# GBxProg.net
KiCad netlist of a schematic drawn in Altium Designer
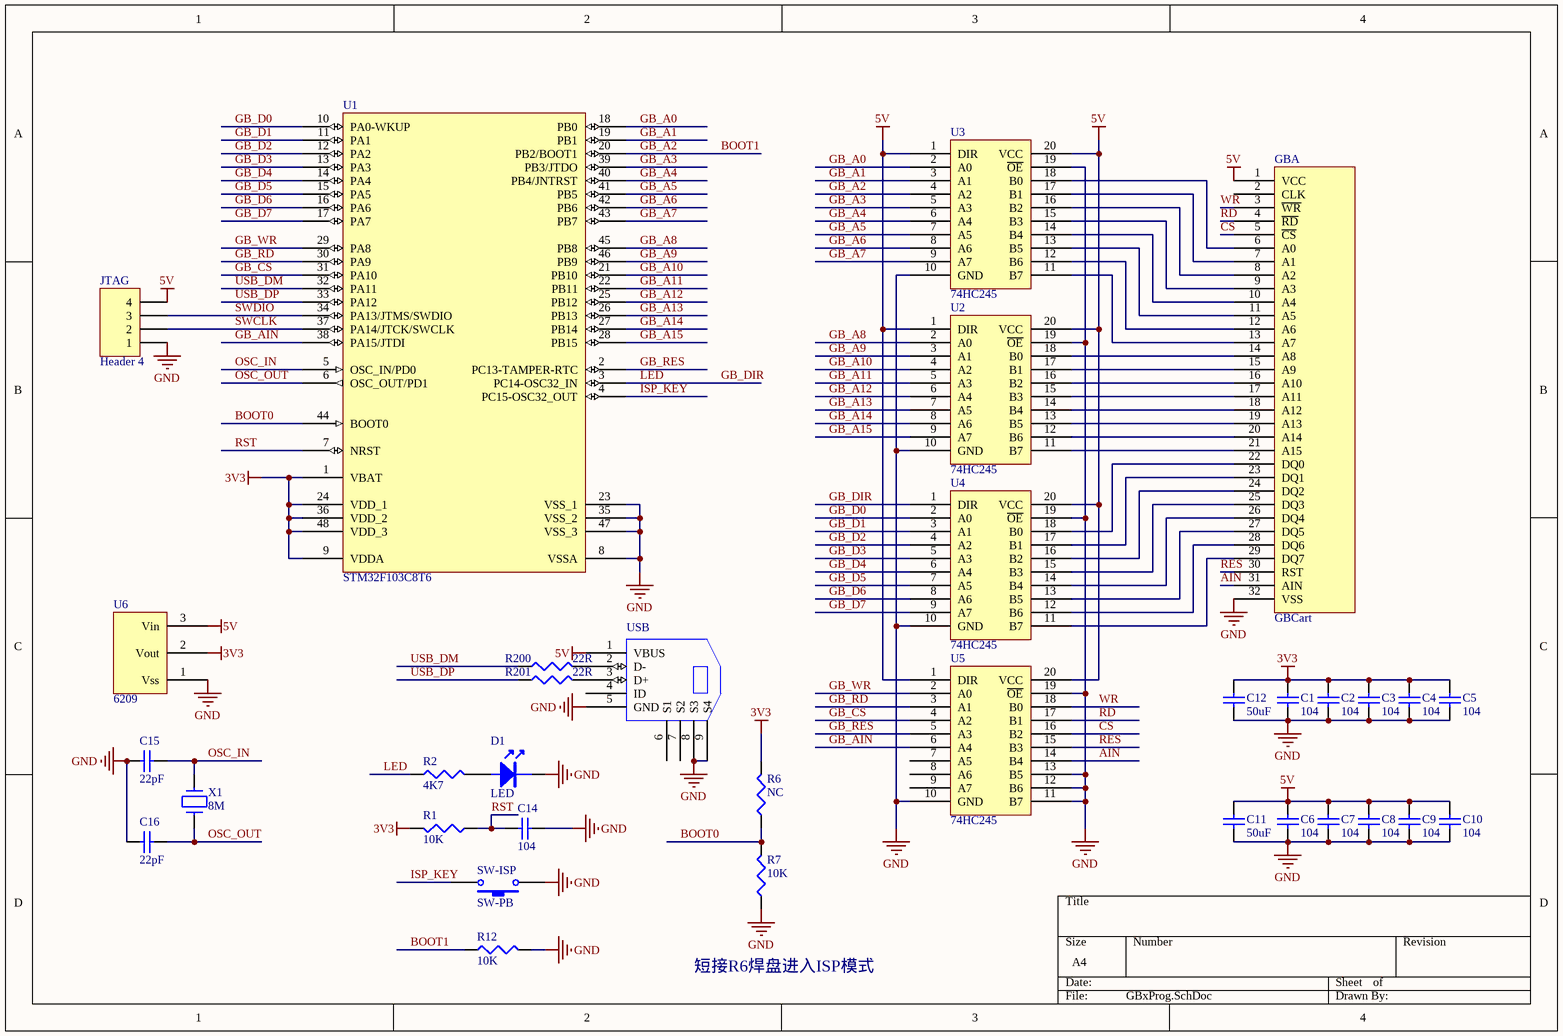
[diagram p0: GBxProg.SchDoc]

(export (version "E")
  (design (tool "Eeschema 10.0.6"))
  (components
    (comp (ref "C1")
      (value "104")
      (footprint "1608[0603]")
      (description "Capacitor (Semiconductor SIM Model)")
      (fields (field (name "PUBLISHER") "Altium Limited"))
      (libsource (lib "Miscellaneous Devices") (part "Cap Semi"))
    )
    (comp (ref "C2")
      (value "104")
      (footprint "1608[0603]")
      (description "Capacitor (Semiconductor SIM Model)")
      (fields (field (name "PUBLISHER") "Altium Limited"))
      (libsource (lib "Miscellaneous Devices") (part "Cap Semi"))
    )
    (comp (ref "C3")
      (value "104")
      (footprint "1608[0603]")
      (description "Capacitor (Semiconductor SIM Model)")
      (fields (field (name "PUBLISHER") "Altium Limited"))
      (libsource (lib "Miscellaneous Devices") (part "Cap Semi"))
    )
    (comp (ref "C4")
      (value "104")
      (footprint "1608[0603]")
      (description "Capacitor (Semiconductor SIM Model)")
      (fields (field (name "PUBLISHER") "Altium Limited"))
      (libsource (lib "Miscellaneous Devices") (part "Cap Semi"))
    )
    (comp (ref "C5")
      (value "104")
      (footprint "1608[0603]")
      (description "Capacitor (Semiconductor SIM Model)")
      (fields (field (name "PUBLISHER") "Altium Limited"))
      (libsource (lib "Miscellaneous Devices") (part "Cap Semi"))
    )
    (comp (ref "C6")
      (value "104")
      (footprint "1608[0603]")
      (description "Capacitor (Semiconductor SIM Model)")
      (fields (field (name "PUBLISHER") "Altium Limited"))
      (libsource (lib "Miscellaneous Devices") (part "Cap Semi"))
    )
    (comp (ref "C7")
      (value "104")
      (footprint "1608[0603]")
      (description "Capacitor (Semiconductor SIM Model)")
      (fields (field (name "PUBLISHER") "Altium Limited"))
      (libsource (lib "Miscellaneous Devices") (part "Cap Semi"))
    )
    (comp (ref "C8")
      (value "104")
      (footprint "1608[0603]")
      (description "Capacitor (Semiconductor SIM Model)")
      (fields (field (name "PUBLISHER") "Altium Limited"))
      (libsource (lib "Miscellaneous Devices") (part "Cap Semi"))
    )
    (comp (ref "C9")
      (value "104")
      (footprint "1608[0603]")
      (description "Capacitor (Semiconductor SIM Model)")
      (fields (field (name "PUBLISHER") "Altium Limited"))
      (libsource (lib "Miscellaneous Devices") (part "Cap Semi"))
    )
    (comp (ref "C10")
      (value "104")
      (footprint "1608[0603]")
      (description "Capacitor (Semiconductor SIM Model)")
      (fields (field (name "PUBLISHER") "Altium Limited"))
      (libsource (lib "Miscellaneous Devices") (part "Cap Semi"))
    )
    (comp (ref "C11")
      (value "50uF")
      (footprint "C1206")
      (description "Capacitor (Semiconductor SIM Model)")
      (fields (field (name "PUBLISHER") "Altium Limited"))
      (libsource (lib "Miscellaneous Devices") (part "Cap Semi"))
    )
    (comp (ref "C12")
      (value "50uF")
      (footprint "C1206")
      (description "Capacitor (Semiconductor SIM Model)")
      (fields (field (name "PUBLISHER") "Altium Limited"))
      (libsource (lib "Miscellaneous Devices") (part "Cap Semi"))
    )
    (comp (ref "C14")
      (value "104")
      (footprint "1608[0603]")
      (description "Capacitor (Semiconductor SIM Model)")
      (fields (field (name "PUBLISHER") "Altium Limited"))
      (libsource (lib "Miscellaneous Devices") (part "Cap Semi"))
    )
    (comp (ref "C15")
      (value "22pF")
      (footprint "1608[0603]")
      (description "Capacitor (Semiconductor SIM Model)")
      (fields (field (name "PUBLISHER") "Altium Limited"))
      (libsource (lib "Miscellaneous Devices") (part "Cap Semi"))
    )
    (comp (ref "C16")
      (value "22pF")
      (footprint "1608[0603]")
      (description "Capacitor (Semiconductor SIM Model)")
      (fields (field (name "PUBLISHER") "Altium Limited"))
      (libsource (lib "Miscellaneous Devices") (part "Cap Semi"))
    )
    (comp (ref "D1") (value "LED") (footprint "0805D") (libsource (lib "Schlib1") (part "LED")))
    (comp (ref "GBA") (value "GBCart") (footprint "GB_CART_1") (libsource (lib "Schlib1") (part "GBCart")))
    (comp (ref "JTAG")
      (value "Header 4")
      (footprint "HDR1X4")
      (description "Header, 4-Pin")
      (fields (field (name "PUBLISHER") "Altium Limited"))
      (libsource (lib "Miscellaneous Connectors") (part "Header 4"))
    )
    (comp (ref "R1")
      (value "10K")
      (footprint "J1-0603")
      (description "Resistor")
      (fields (field (name "PUBLISHER") "Altium Limited"))
      (libsource (lib "Miscellaneous Devices") (part "Res3"))
    )
    (comp (ref "R2")
      (value "4K7")
      (footprint "J1-0603")
      (description "Resistor")
      (fields (field (name "PUBLISHER") "Altium Limited"))
      (libsource (lib "Miscellaneous Devices") (part "Res3"))
    )
    (comp (ref "R6")
      (value "NC")
      (footprint "J1-0603")
      (description "Resistor")
      (fields (field (name "PUBLISHER") "Altium Limited"))
      (libsource (lib "Miscellaneous Devices") (part "Res3"))
    )
    (comp (ref "R7")
      (value "10K")
      (footprint "J1-0603")
      (description "Resistor")
      (fields (field (name "PUBLISHER") "Altium Limited"))
      (libsource (lib "Miscellaneous Devices") (part "Res3"))
    )
    (comp (ref "R12")
      (value "10K")
      (footprint "J1-0603")
      (description "Resistor")
      (fields (field (name "PUBLISHER") "Altium Limited"))
      (libsource (lib "Miscellaneous Devices") (part "Res3"))
    )
    (comp (ref "R200")
      (value "22R")
      (footprint "J1-0603")
      (description "Resistor")
      (fields (field (name "PUBLISHER") "Altium Limited"))
      (libsource (lib "Miscellaneous Devices") (part "Res3"))
    )
    (comp (ref "R201")
      (value "22R")
      (footprint "J1-0603")
      (description "Resistor")
      (fields (field (name "PUBLISHER") "Altium Limited"))
      (libsource (lib "Miscellaneous Devices") (part "Res3"))
    )
    (comp (ref "SW-ISP")
      (value "SW-PB")
      (footprint "SOP2")
      (description "Switch")
      (fields (field (name "PUBLISHER") "Altium Limited"))
      (libsource (lib "Miscellaneous Devices") (part "SW-PB"))
    )
    (comp (ref "U1")
      (value "STM32F103C8T6")
      (footprint "LQFP48_N")
      (description "STM32 ARM-based 32-bit MCU with 64 Kbytes Flash, 48-pin LQFP, Industrial Temperature")
      (fields (field (name "PUBLISHER") "*"))
      (libsource (lib "Schlib1") (part "STM32F103C8T6"))
    )
    (comp (ref "U2") (value "74HC245") (footprint "TSSOP20") (libsource (lib "Schlib1") (part "74HC245")))
    (comp (ref "U3") (value "74HC245") (footprint "TSSOP20") (libsource (lib "Schlib1") (part "74HC245")))
    (comp (ref "U4") (value "74HC245") (footprint "TSSOP20") (libsource (lib "Schlib1") (part "74HC245")))
    (comp (ref "U5") (value "74HC245") (footprint "TSSOP20") (libsource (lib "Schlib1") (part "74HC245")))
    (comp (ref "U6") (value "6209") (footprint "SOT-23") (libsource (lib "Schlib1") (part "6209")))
    (comp (ref "USB") (value "USB-MINIAB") (footprint "USB-MICRO") (libsource (lib "*") (part "USB-MINIAB")))
    (comp (ref "X1") (value "8M") (footprint "49S") (libsource (lib "常用元件库") (part "CRYSTAL")))
  )
  (nets
    (net (code "1") (name "/AIN") (class "Default")
      (node (ref "GBA") (pin "31") (pinfunction "AIN_31") (pintype "passive"))
      (node (ref "U5") (pin "14") (pinfunction "B4_14") (pintype "passive"))
    )
    (net (code "2") (name "/BOOT0") (class "Default")
      (node (ref "R6") (pin "1") (pinfunction "1_1") (pintype "passive"))
      (node (ref "R7") (pin "2") (pinfunction "2_2") (pintype "passive"))
      (node (ref "U1") (pin "44") (pinfunction "BOOT0_44") (pintype "input"))
    )
    (net (code "3") (name "/BOOT1") (class "Default")
      (node (ref "R12") (pin "1") (pinfunction "1_1") (pintype "passive"))
      (node (ref "U1") (pin "20") (pinfunction "PB2/BOOT1_20") (pintype "bidirectional"))
      (node (ref "U3") (pin "4") (pinfunction "A2_4") (pintype "passive"))
    )
    (net (code "4") (name "/CS") (class "Default")
      (node (ref "GBA") (pin "5") (pinfunction "~{CS}_5") (pintype "passive"))
      (node (ref "U5") (pin "16") (pinfunction "B2_16") (pintype "passive"))
    )
    (net (code "5") (name "/GB_A0") (class "Default")
      (node (ref "U1") (pin "18") (pinfunction "PB0_18") (pintype "bidirectional"))
      (node (ref "U3") (pin "2") (pinfunction "A0_2") (pintype "passive"))
    )
    (net (code "6") (name "/GB_A1") (class "Default")
      (node (ref "U1") (pin "19") (pinfunction "PB1_19") (pintype "bidirectional"))
      (node (ref "U3") (pin "3") (pinfunction "A1_3") (pintype "passive"))
    )
    (net (code "7") (name "/GB_A3") (class "Default")
      (node (ref "U1") (pin "39") (pinfunction "PB3/JTDO_39") (pintype "bidirectional"))
      (node (ref "U3") (pin "5") (pinfunction "A3_5") (pintype "passive"))
    )
    (net (code "8") (name "/GB_A4") (class "Default")
      (node (ref "U1") (pin "40") (pinfunction "PB4/JNTRST_40") (pintype "bidirectional"))
      (node (ref "U3") (pin "6") (pinfunction "A4_6") (pintype "passive"))
    )
    (net (code "9") (name "/GB_A5") (class "Default")
      (node (ref "U1") (pin "41") (pinfunction "PB5_41") (pintype "bidirectional"))
      (node (ref "U3") (pin "7") (pinfunction "A5_7") (pintype "passive"))
    )
    (net (code "10") (name "/GB_A6") (class "Default")
      (node (ref "U1") (pin "42") (pinfunction "PB6_42") (pintype "bidirectional"))
      (node (ref "U3") (pin "8") (pinfunction "A6_8") (pintype "passive"))
    )
    (net (code "11") (name "/GB_A7") (class "Default")
      (node (ref "U1") (pin "43") (pinfunction "PB7_43") (pintype "bidirectional"))
      (node (ref "U3") (pin "9") (pinfunction "A7_9") (pintype "passive"))
    )
    (net (code "12") (name "/GB_A8") (class "Default")
      (node (ref "U1") (pin "45") (pinfunction "PB8_45") (pintype "bidirectional"))
      (node (ref "U2") (pin "2") (pinfunction "A0_2") (pintype "passive"))
    )
    (net (code "13") (name "/GB_A9") (class "Default")
      (node (ref "U1") (pin "46") (pinfunction "PB9_46") (pintype "bidirectional"))
      (node (ref "U2") (pin "3") (pinfunction "A1_3") (pintype "passive"))
    )
    (net (code "14") (name "/GB_A10") (class "Default")
      (node (ref "U1") (pin "21") (pinfunction "PB10_21") (pintype "bidirectional"))
      (node (ref "U2") (pin "4") (pinfunction "A2_4") (pintype "passive"))
    )
    (net (code "15") (name "/GB_A11") (class "Default")
      (node (ref "U1") (pin "22") (pinfunction "PB11_22") (pintype "bidirectional"))
      (node (ref "U2") (pin "5") (pinfunction "A3_5") (pintype "passive"))
    )
    (net (code "16") (name "/GB_A12") (class "Default")
      (node (ref "U1") (pin "25") (pinfunction "PB12_25") (pintype "bidirectional"))
      (node (ref "U2") (pin "6") (pinfunction "A4_6") (pintype "passive"))
    )
    (net (code "17") (name "/GB_A13") (class "Default")
      (node (ref "U1") (pin "26") (pinfunction "PB13_26") (pintype "bidirectional"))
      (node (ref "U2") (pin "7") (pinfunction "A5_7") (pintype "passive"))
    )
    (net (code "18") (name "/GB_A14") (class "Default")
      (node (ref "U1") (pin "27") (pinfunction "PB14_27") (pintype "bidirectional"))
      (node (ref "U2") (pin "8") (pinfunction "A6_8") (pintype "passive"))
    )
    (net (code "19") (name "/GB_A15") (class "Default")
      (node (ref "U1") (pin "28") (pinfunction "PB15_28") (pintype "bidirectional"))
      (node (ref "U2") (pin "9") (pinfunction "A7_9") (pintype "passive"))
    )
    (net (code "20") (name "/GB_AIN") (class "Default")
      (node (ref "U1") (pin "38") (pinfunction "PA15/JTDI_38") (pintype "bidirectional"))
      (node (ref "U5") (pin "6") (pinfunction "A4_6") (pintype "passive"))
    )
    (net (code "21") (name "/GB_CS") (class "Default")
      (node (ref "U1") (pin "31") (pinfunction "PA10_31") (pintype "bidirectional"))
      (node (ref "U5") (pin "4") (pinfunction "A2_4") (pintype "passive"))
    )
    (net (code "22") (name "/GB_D0") (class "Default")
      (node (ref "U1") (pin "10") (pinfunction "PA0-WKUP_10") (pintype "bidirectional"))
      (node (ref "U4") (pin "2") (pinfunction "A0_2") (pintype "passive"))
    )
    (net (code "23") (name "/GB_D1") (class "Default")
      (node (ref "U1") (pin "11") (pinfunction "PA1_11") (pintype "bidirectional"))
      (node (ref "U4") (pin "3") (pinfunction "A1_3") (pintype "passive"))
    )
    (net (code "24") (name "/GB_D2") (class "Default")
      (node (ref "U1") (pin "12") (pinfunction "PA2_12") (pintype "bidirectional"))
      (node (ref "U4") (pin "4") (pinfunction "A2_4") (pintype "passive"))
    )
    (net (code "25") (name "/GB_D3") (class "Default")
      (node (ref "U1") (pin "13") (pinfunction "PA3_13") (pintype "bidirectional"))
      (node (ref "U4") (pin "5") (pinfunction "A3_5") (pintype "passive"))
    )
    (net (code "26") (name "/GB_D4") (class "Default")
      (node (ref "U1") (pin "14") (pinfunction "PA4_14") (pintype "bidirectional"))
      (node (ref "U4") (pin "6") (pinfunction "A4_6") (pintype "passive"))
    )
    (net (code "27") (name "/GB_D5") (class "Default")
      (node (ref "U1") (pin "15") (pinfunction "PA5_15") (pintype "bidirectional"))
      (node (ref "U4") (pin "7") (pinfunction "A5_7") (pintype "passive"))
    )
    (net (code "28") (name "/GB_D6") (class "Default")
      (node (ref "U1") (pin "16") (pinfunction "PA6_16") (pintype "bidirectional"))
      (node (ref "U4") (pin "8") (pinfunction "A6_8") (pintype "passive"))
    )
    (net (code "29") (name "/GB_D7") (class "Default")
      (node (ref "U1") (pin "17") (pinfunction "PA7_17") (pintype "bidirectional"))
      (node (ref "U4") (pin "9") (pinfunction "A7_9") (pintype "passive"))
    )
    (net (code "30") (name "/GB_DIR") (class "Default")
      (node (ref "R2") (pin "1") (pinfunction "1_1") (pintype "passive"))
      (node (ref "U1") (pin "3") (pinfunction "PC14-OSC32_IN_3") (pintype "bidirectional"))
      (node (ref "U4") (pin "1") (pinfunction "DIR_1") (pintype "passive"))
    )
    (net (code "31") (name "/GB_RD") (class "Default")
      (node (ref "U1") (pin "30") (pinfunction "PA9_30") (pintype "bidirectional"))
      (node (ref "U5") (pin "3") (pinfunction "A1_3") (pintype "passive"))
    )
    (net (code "32") (name "/GB_RES") (class "Default")
      (node (ref "U1") (pin "2") (pinfunction "PC13-TAMPER-RTC_2") (pintype "bidirectional"))
      (node (ref "U5") (pin "5") (pinfunction "A3_5") (pintype "passive"))
    )
    (net (code "33") (name "/GB_WR") (class "Default")
      (node (ref "U1") (pin "29") (pinfunction "PA8_29") (pintype "bidirectional"))
      (node (ref "U5") (pin "2") (pinfunction "A0_2") (pintype "passive"))
    )
    (net (code "34") (name "/ISP_KEY") (class "Default")
      (node (ref "SW-ISP") (pin "2") (pinfunction "2_2") (pintype "passive"))
      (node (ref "U1") (pin "4") (pinfunction "PC15-OSC32_OUT_4") (pintype "bidirectional"))
    )
    (net (code "35") (name "/OSC_IN") (class "Default")
      (node (ref "C15") (pin "1") (pinfunction "1_1") (pintype "passive"))
      (node (ref "U1") (pin "5") (pinfunction "OSC_IN/PD0_5") (pintype "input"))
      (node (ref "X1") (pin "2") (pinfunction "2_2") (pintype "passive"))
    )
    (net (code "36") (name "/OSC_OUT") (class "Default")
      (node (ref "C16") (pin "1") (pinfunction "1_1") (pintype "passive"))
      (node (ref "U1") (pin "6") (pinfunction "OSC_OUT/PD1_6") (pintype "output"))
      (node (ref "X1") (pin "1") (pinfunction "1_1") (pintype "passive"))
    )
    (net (code "37") (name "/RD") (class "Default")
      (node (ref "GBA") (pin "4") (pinfunction "~{RD}_4") (pintype "passive"))
      (node (ref "U5") (pin "17") (pinfunction "B1_17") (pintype "passive"))
    )
    (net (code "38") (name "/RES") (class "Default")
      (node (ref "GBA") (pin "30") (pinfunction "RST_30") (pintype "passive"))
      (node (ref "U5") (pin "15") (pinfunction "B3_15") (pintype "passive"))
    )
    (net (code "39") (name "/RST") (class "Default")
      (node (ref "C14") (pin "2") (pinfunction "2_2") (pintype "passive"))
      (node (ref "R1") (pin "1") (pinfunction "1_1") (pintype "passive"))
      (node (ref "U1") (pin "7") (pinfunction "NRST_7") (pintype "bidirectional"))
    )
    (net (code "40") (name "/SWCLK") (class "Default")
      (node (ref "JTAG") (pin "2") (pinfunction "2_2") (pintype "passive"))
      (node (ref "U1") (pin "37") (pinfunction "PA14/JTCK/SWCLK_37") (pintype "bidirectional"))
    )
    (net (code "41") (name "/SWDIO") (class "Default")
      (node (ref "JTAG") (pin "3") (pinfunction "3_3") (pintype "passive"))
      (node (ref "U1") (pin "34") (pinfunction "PA13/JTMS/SWDIO_34") (pintype "bidirectional"))
    )
    (net (code "42") (name "/USB_DM") (class "Default")
      (node (ref "R200") (pin "1") (pinfunction "1_1") (pintype "passive"))
      (node (ref "U1") (pin "32") (pinfunction "PA11_32") (pintype "bidirectional"))
    )
    (net (code "43") (name "/USB_DP") (class "Default")
      (node (ref "R201") (pin "1") (pinfunction "1_1") (pintype "passive"))
      (node (ref "U1") (pin "33") (pinfunction "PA12_33") (pintype "bidirectional"))
    )
    (net (code "44") (name "/WR") (class "Default")
      (node (ref "GBA") (pin "3") (pinfunction "~{WR}_3") (pintype "passive"))
      (node (ref "U5") (pin "18") (pinfunction "B0_18") (pintype "passive"))
    )
    (net (code "45") (name "3V3") (class "Default")
      (node (ref "C1") (pin "2") (pinfunction "2_2") (pintype "passive"))
      (node (ref "C12") (pin "2") (pinfunction "2_2") (pintype "passive"))
      (node (ref "C2") (pin "2") (pinfunction "2_2") (pintype "passive"))
      (node (ref "C3") (pin "2") (pinfunction "2_2") (pintype "passive"))
      (node (ref "C4") (pin "2") (pinfunction "2_2") (pintype "passive"))
      (node (ref "C5") (pin "2") (pinfunction "2_2") (pintype "passive"))
      (node (ref "R1") (pin "2") (pinfunction "2_2") (pintype "passive"))
      (node (ref "R6") (pin "2") (pinfunction "2_2") (pintype "passive"))
      (node (ref "U1") (pin "1") (pinfunction "VBAT_1") (pintype "power_in"))
      (node (ref "U1") (pin "24") (pinfunction "VDD_1_24") (pintype "power_in"))
      (node (ref "U1") (pin "36") (pinfunction "VDD_2_36") (pintype "power_in"))
      (node (ref "U1") (pin "48") (pinfunction "VDD_3_48") (pintype "power_in"))
      (node (ref "U1") (pin "9") (pinfunction "VDDA_9") (pintype "power_in"))
      (node (ref "U6") (pin "2") (pinfunction "Vout_2") (pintype "passive"))
    )
    (net (code "46") (name "5V") (class "Default")
      (node (ref "C10") (pin "2") (pinfunction "2_2") (pintype "passive"))
      (node (ref "C11") (pin "2") (pinfunction "2_2") (pintype "passive"))
      (node (ref "C6") (pin "2") (pinfunction "2_2") (pintype "passive"))
      (node (ref "C7") (pin "2") (pinfunction "2_2") (pintype "passive"))
      (node (ref "C8") (pin "2") (pinfunction "2_2") (pintype "passive"))
      (node (ref "C9") (pin "2") (pinfunction "2_2") (pintype "passive"))
      (node (ref "GBA") (pin "1") (pinfunction "VCC_1") (pintype "passive"))
      (node (ref "JTAG") (pin "4") (pinfunction "4_4") (pintype "passive"))
      (node (ref "U2") (pin "1") (pinfunction "DIR_1") (pintype "passive"))
      (node (ref "U2") (pin "20") (pinfunction "VCC_20") (pintype "passive"))
      (node (ref "U3") (pin "1") (pinfunction "DIR_1") (pintype "passive"))
      (node (ref "U3") (pin "20") (pinfunction "VCC_20") (pintype "passive"))
      (node (ref "U4") (pin "20") (pinfunction "VCC_20") (pintype "passive"))
      (node (ref "U5") (pin "1") (pinfunction "DIR_1") (pintype "passive"))
      (node (ref "U5") (pin "20") (pinfunction "VCC_20") (pintype "passive"))
      (node (ref "U6") (pin "3") (pinfunction "Vin_3") (pintype "passive"))
      (node (ref "USB") (pin "1") (pinfunction "VBUS_1") (pintype "passive"))
    )
    (net (code "47") (name "GND") (class "Default")
      (node (ref "C1") (pin "1") (pinfunction "1_1") (pintype "passive"))
      (node (ref "C10") (pin "1") (pinfunction "1_1") (pintype "passive"))
      (node (ref "C11") (pin "1") (pinfunction "1_1") (pintype "passive"))
      (node (ref "C12") (pin "1") (pinfunction "1_1") (pintype "passive"))
      (node (ref "C14") (pin "1") (pinfunction "1_1") (pintype "passive"))
      (node (ref "C15") (pin "2") (pinfunction "2_2") (pintype "passive"))
      (node (ref "C16") (pin "2") (pinfunction "2_2") (pintype "passive"))
      (node (ref "C2") (pin "1") (pinfunction "1_1") (pintype "passive"))
      (node (ref "C3") (pin "1") (pinfunction "1_1") (pintype "passive"))
      (node (ref "C4") (pin "1") (pinfunction "1_1") (pintype "passive"))
      (node (ref "C5") (pin "1") (pinfunction "1_1") (pintype "passive"))
      (node (ref "C6") (pin "1") (pinfunction "1_1") (pintype "passive"))
      (node (ref "C7") (pin "1") (pinfunction "1_1") (pintype "passive"))
      (node (ref "C8") (pin "1") (pinfunction "1_1") (pintype "passive"))
      (node (ref "C9") (pin "1") (pinfunction "1_1") (pintype "passive"))
      (node (ref "D1") (pin "K") (pinfunction "2_K") (pintype "passive"))
      (node (ref "GBA") (pin "32") (pinfunction "VSS_32") (pintype "passive"))
      (node (ref "JTAG") (pin "1") (pinfunction "1_1") (pintype "passive"))
      (node (ref "R12") (pin "2") (pinfunction "2_2") (pintype "passive"))
      (node (ref "R7") (pin "1") (pinfunction "1_1") (pintype "passive"))
      (node (ref "SW-ISP") (pin "1") (pinfunction "1_1") (pintype "passive"))
      (node (ref "U1") (pin "23") (pinfunction "VSS_1_23") (pintype "power_in"))
      (node (ref "U1") (pin "35") (pinfunction "VSS_2_35") (pintype "power_in"))
      (node (ref "U1") (pin "47") (pinfunction "VSS_3_47") (pintype "power_in"))
      (node (ref "U1") (pin "8") (pinfunction "VSSA_8") (pintype "power_in"))
      (node (ref "U2") (pin "10") (pinfunction "GND_10") (pintype "passive"))
      (node (ref "U2") (pin "19") (pinfunction "~{OE}_19") (pintype "passive"))
      (node (ref "U3") (pin "10") (pinfunction "GND_10") (pintype "passive"))
      (node (ref "U3") (pin "19") (pinfunction "~{OE}_19") (pintype "passive"))
      (node (ref "U4") (pin "10") (pinfunction "GND_10") (pintype "passive"))
      (node (ref "U4") (pin "19") (pinfunction "~{OE}_19") (pintype "passive"))
      (node (ref "U5") (pin "10") (pinfunction "GND_10") (pintype "passive"))
      (node (ref "U5") (pin "11") (pinfunction "B7_11") (pintype "passive"))
      (node (ref "U5") (pin "12") (pinfunction "B6_12") (pintype "passive"))
      (node (ref "U5") (pin "13") (pinfunction "B5_13") (pintype "passive"))
      (node (ref "U5") (pin "19") (pinfunction "~{OE}_19") (pintype "passive"))
      (node (ref "U6") (pin "1") (pinfunction "Vss_1") (pintype "passive"))
      (node (ref "USB") (pin "5") (pinfunction "GND_5") (pintype "power_in"))
      (node (ref "USB") (pin "8") (pinfunction "S3_8") (pintype "passive"))
      (node (ref "USB") (pin "9") (pinfunction "S4_9") (pintype "passive"))
    )
    (net (code "48") (name "Net-(D1-1)") (class "Default")
      (node (ref "D1") (pin "A") (pinfunction "1_A") (pintype "passive"))
      (node (ref "R2") (pin "2") (pinfunction "2_2") (pintype "passive"))
    )
    (net (code "49") (name "Net-(GBA-A0)") (class "Default")
      (node (ref "GBA") (pin "6") (pinfunction "A0_6") (pintype "passive"))
      (node (ref "U3") (pin "18") (pinfunction "B0_18") (pintype "passive"))
    )
    (net (code "50") (name "Net-(GBA-A1)") (class "Default")
      (node (ref "GBA") (pin "7") (pinfunction "A1_7") (pintype "passive"))
      (node (ref "U3") (pin "17") (pinfunction "B1_17") (pintype "passive"))
    )
    (net (code "51") (name "Net-(GBA-A2)") (class "Default")
      (node (ref "GBA") (pin "8") (pinfunction "A2_8") (pintype "passive"))
      (node (ref "U3") (pin "16") (pinfunction "B2_16") (pintype "passive"))
    )
    (net (code "52") (name "Net-(GBA-A3)") (class "Default")
      (node (ref "GBA") (pin "9") (pinfunction "A3_9") (pintype "passive"))
      (node (ref "U3") (pin "15") (pinfunction "B3_15") (pintype "passive"))
    )
    (net (code "53") (name "Net-(GBA-A4)") (class "Default")
      (node (ref "GBA") (pin "10") (pinfunction "A4_10") (pintype "passive"))
      (node (ref "U3") (pin "14") (pinfunction "B4_14") (pintype "passive"))
    )
    (net (code "54") (name "Net-(GBA-A5)") (class "Default")
      (node (ref "GBA") (pin "11") (pinfunction "A5_11") (pintype "passive"))
      (node (ref "U3") (pin "13") (pinfunction "B5_13") (pintype "passive"))
    )
    (net (code "55") (name "Net-(GBA-A6)") (class "Default")
      (node (ref "GBA") (pin "12") (pinfunction "A6_12") (pintype "passive"))
      (node (ref "U3") (pin "12") (pinfunction "B6_12") (pintype "passive"))
    )
    (net (code "56") (name "Net-(GBA-A7)") (class "Default")
      (node (ref "GBA") (pin "13") (pinfunction "A7_13") (pintype "passive"))
      (node (ref "U3") (pin "11") (pinfunction "B7_11") (pintype "passive"))
    )
    (net (code "57") (name "Net-(GBA-A8)") (class "Default")
      (node (ref "GBA") (pin "14") (pinfunction "A8_14") (pintype "passive"))
      (node (ref "U2") (pin "18") (pinfunction "B0_18") (pintype "passive"))
    )
    (net (code "58") (name "Net-(GBA-A9)") (class "Default")
      (node (ref "GBA") (pin "15") (pinfunction "A9_15") (pintype "passive"))
      (node (ref "U2") (pin "17") (pinfunction "B1_17") (pintype "passive"))
    )
    (net (code "59") (name "Net-(GBA-A10)") (class "Default")
      (node (ref "GBA") (pin "16") (pinfunction "A10_16") (pintype "passive"))
      (node (ref "U2") (pin "16") (pinfunction "B2_16") (pintype "passive"))
    )
    (net (code "60") (name "Net-(GBA-A11)") (class "Default")
      (node (ref "GBA") (pin "17") (pinfunction "A11_17") (pintype "passive"))
      (node (ref "U2") (pin "15") (pinfunction "B3_15") (pintype "passive"))
    )
    (net (code "61") (name "Net-(GBA-A12)") (class "Default")
      (node (ref "GBA") (pin "18") (pinfunction "A12_18") (pintype "passive"))
      (node (ref "U2") (pin "14") (pinfunction "B4_14") (pintype "passive"))
    )
    (net (code "62") (name "Net-(GBA-A13)") (class "Default")
      (node (ref "GBA") (pin "19") (pinfunction "A13_19") (pintype "passive"))
      (node (ref "U2") (pin "13") (pinfunction "B5_13") (pintype "passive"))
    )
    (net (code "63") (name "Net-(GBA-A14)") (class "Default")
      (node (ref "GBA") (pin "20") (pinfunction "A14_20") (pintype "passive"))
      (node (ref "U2") (pin "12") (pinfunction "B6_12") (pintype "passive"))
    )
    (net (code "64") (name "Net-(GBA-A15)") (class "Default")
      (node (ref "GBA") (pin "21") (pinfunction "A15_21") (pintype "passive"))
      (node (ref "U2") (pin "11") (pinfunction "B7_11") (pintype "passive"))
    )
    (net (code "65") (name "Net-(GBA-DQ0)") (class "Default")
      (node (ref "GBA") (pin "22") (pinfunction "DQ0_22") (pintype "passive"))
      (node (ref "U4") (pin "18") (pinfunction "B0_18") (pintype "passive"))
    )
    (net (code "66") (name "Net-(GBA-DQ1)") (class "Default")
      (node (ref "GBA") (pin "23") (pinfunction "DQ1_23") (pintype "passive"))
      (node (ref "U4") (pin "17") (pinfunction "B1_17") (pintype "passive"))
    )
    (net (code "67") (name "Net-(GBA-DQ2)") (class "Default")
      (node (ref "GBA") (pin "24") (pinfunction "DQ2_24") (pintype "passive"))
      (node (ref "U4") (pin "16") (pinfunction "B2_16") (pintype "passive"))
    )
    (net (code "68") (name "Net-(GBA-DQ3)") (class "Default")
      (node (ref "GBA") (pin "25") (pinfunction "DQ3_25") (pintype "passive"))
      (node (ref "U4") (pin "15") (pinfunction "B3_15") (pintype "passive"))
    )
    (net (code "69") (name "Net-(GBA-DQ4)") (class "Default")
      (node (ref "GBA") (pin "26") (pinfunction "DQ4_26") (pintype "passive"))
      (node (ref "U4") (pin "14") (pinfunction "B4_14") (pintype "passive"))
    )
    (net (code "70") (name "Net-(GBA-DQ5)") (class "Default")
      (node (ref "GBA") (pin "27") (pinfunction "DQ5_27") (pintype "passive"))
      (node (ref "U4") (pin "13") (pinfunction "B5_13") (pintype "passive"))
    )
    (net (code "71") (name "Net-(GBA-DQ6)") (class "Default")
      (node (ref "GBA") (pin "28") (pinfunction "DQ6_28") (pintype "passive"))
      (node (ref "U4") (pin "12") (pinfunction "B6_12") (pintype "passive"))
    )
    (net (code "72") (name "Net-(GBA-DQ7)") (class "Default")
      (node (ref "GBA") (pin "29") (pinfunction "DQ7_29") (pintype "passive"))
      (node (ref "U4") (pin "11") (pinfunction "B7_11") (pintype "passive"))
    )
    (net (code "73") (name "Net-(USB-D+)") (class "Default")
      (node (ref "R201") (pin "2") (pinfunction "2_2") (pintype "passive"))
      (node (ref "USB") (pin "3") (pinfunction "D+_3") (pintype "bidirectional"))
    )
    (net (code "74") (name "Net-(USB-D-)") (class "Default")
      (node (ref "R200") (pin "2") (pinfunction "2_2") (pintype "passive"))
      (node (ref "USB") (pin "2") (pinfunction "D-_2") (pintype "bidirectional"))
    )
    (net (code "75") (name "unconnected-(GBA-CLK-Pad2)") (class "Default")
      (node (ref "GBA") (pin "2") (pinfunction "CLK_2") (pintype "passive"))
    )
    (net (code "76") (name "unconnected-(U5-A5-Pad7)") (class "Default")
      (node (ref "U5") (pin "7") (pinfunction "A5_7") (pintype "passive"))
    )
    (net (code "77") (name "unconnected-(U5-A6-Pad8)") (class "Default")
      (node (ref "U5") (pin "8") (pinfunction "A6_8") (pintype "passive"))
    )
    (net (code "78") (name "unconnected-(U5-A7-Pad9)") (class "Default")
      (node (ref "U5") (pin "9") (pinfunction "A7_9") (pintype "passive"))
    )
    (net (code "79") (name "unconnected-(USB-ID-Pad4)") (class "Default")
      (node (ref "USB") (pin "4") (pinfunction "ID_4") (pintype "passive"))
    )
    (net (code "80") (name "unconnected-(USB-S1-Pad6)") (class "Default")
      (node (ref "USB") (pin "6") (pinfunction "S1_6") (pintype "passive"))
    )
    (net (code "81") (name "unconnected-(USB-S2-Pad7)") (class "Default")
      (node (ref "USB") (pin "7") (pinfunction "S2_7") (pintype "passive"))
    )
  )
)
